# TL431_Fan_Control.net
KiCad netlist of a schematic drawn in EAGLE
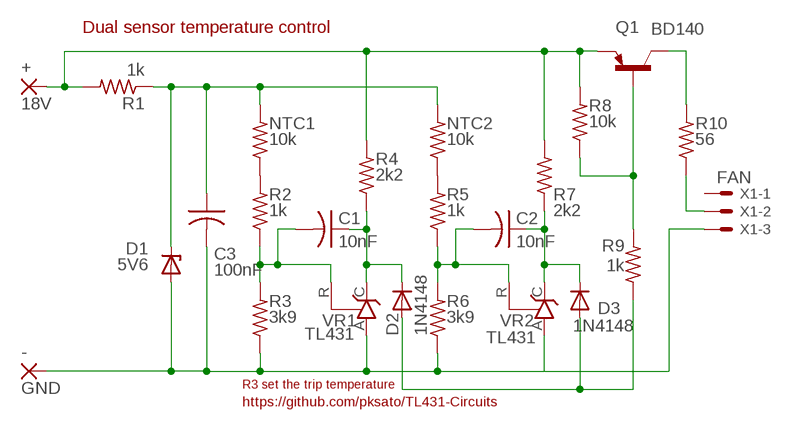
[diagram p0: schematic, sheet 1]

(export (version "E")
  (design (tool "Eeschema 10.0.6"))
  (components
    (comp (ref "+")
      (value "18V")
      (footprint "eagle-import:2,54_1,0")
      (libsource (lib "eagle-import") (part "WIREPAD2,54/1,0"))
    )
    (comp (ref "-")
      (value "GND")
      (footprint "eagle-import:2,54_1,0")
      (libsource (lib "eagle-import") (part "WIREPAD2,54/1,0"))
    )
    (comp (ref "C1")
      (value "10nF")
      (footprint "eagle-import:C050-024X044")
      (libsource (lib "eagle-import") (part "C-US050-024X044"))
    )
    (comp (ref "C2")
      (value "10nF")
      (footprint "eagle-import:C050-024X044")
      (libsource (lib "eagle-import") (part "C-US050-024X044"))
    )
    (comp (ref "C3")
      (value "100nF")
      (footprint "eagle-import:C050-024X044")
      (libsource (lib "eagle-import") (part "C-US050-024X044"))
    )
    (comp (ref "D1")
      (value "5V6")
      (footprint "eagle-import:ZDIO-7.5")
      (libsource (lib "eagle-import") (part "ZENER-DIODEZD-7.5"))
    )
    (comp (ref "D2")
      (value "1N4148")
      (footprint "eagle-import:D-5")
      (libsource (lib "eagle-import") (part "DIODE-D-5"))
    )
    (comp (ref "D3")
      (value "1N4148")
      (footprint "eagle-import:D-5")
      (libsource (lib "eagle-import") (part "DIODE-D-5"))
    )
    (comp (ref "NTC1")
      (value "10k")
      (footprint "eagle-import:0207_2V")
      (libsource (lib "eagle-import") (part "R-US_0207/2V"))
    )
    (comp (ref "NTC2")
      (value "10k")
      (footprint "eagle-import:0207_2V")
      (libsource (lib "eagle-import") (part "R-US_0207/2V"))
    )
    (comp (ref "Q1")
      (value "BD140")
      (footprint "eagle-import:TO126")
      (libsource (lib "eagle-import") (part "BD140"))
    )
    (comp (ref "R1")
      (value "1k")
      (footprint "eagle-import:0207_10")
      (libsource (lib "eagle-import") (part "R-US_0207/10"))
    )
    (comp (ref "R2")
      (value "1k")
      (footprint "eagle-import:0207_10")
      (libsource (lib "eagle-import") (part "R-US_0207/10"))
    )
    (comp (ref "R3")
      (value "3k9")
      (footprint "eagle-import:0207_10")
      (libsource (lib "eagle-import") (part "R-US_0207/10"))
    )
    (comp (ref "R4")
      (value "2k2")
      (footprint "eagle-import:0207_10")
      (libsource (lib "eagle-import") (part "R-US_0207/10"))
    )
    (comp (ref "R5")
      (value "1k")
      (footprint "eagle-import:0207_10")
      (libsource (lib "eagle-import") (part "R-US_0207/10"))
    )
    (comp (ref "R6")
      (value "3k9")
      (footprint "eagle-import:0207_10")
      (libsource (lib "eagle-import") (part "R-US_0207/10"))
    )
    (comp (ref "R7")
      (value "2k2")
      (footprint "eagle-import:0207_10")
      (libsource (lib "eagle-import") (part "R-US_0207/10"))
    )
    (comp (ref "R8")
      (value "10k")
      (footprint "eagle-import:0207_10")
      (libsource (lib "eagle-import") (part "R-US_0207/10"))
    )
    (comp (ref "R9")
      (value "1k")
      (footprint "eagle-import:0207_10")
      (libsource (lib "eagle-import") (part "R-US_0207/10"))
    )
    (comp (ref "R10")
      (value "56")
      (footprint "eagle-import:0617_22")
      (libsource (lib "eagle-import") (part "R-US_0617/22"))
    )
    (comp (ref "VR1")
      (value "TL431")
      (footprint "eagle-import:TO92-CLP")
      (libsource (lib "eagle-import") (part "TL431CLP"))
    )
    (comp (ref "VR2")
      (value "TL431")
      (footprint "eagle-import:TO92-CLP")
      (libsource (lib "eagle-import") (part "TL431CLP"))
    )
    (comp (ref "X1")
      (value "FAN")
      (footprint "eagle-import:22-23-2031")
      (fields (field (name "MF") "MOLEX") (field (name "MPN") "22-23-2031"))
      (libsource (lib "eagle-import") (part "22-23-2031"))
    )
  )
  (nets
    (net (code "1") (name "Net-(+-P)") (class "Default")
      (node (ref "+") (pin "1") (pinfunction "P_1") (pintype "passive"))
      (node (ref "Q1") (pin "1") (pinfunction "E_1") (pintype "passive"))
      (node (ref "R1") (pin "2") (pinfunction "2_2") (pintype "passive"))
      (node (ref "R4") (pin "2") (pinfunction "2_2") (pintype "passive"))
      (node (ref "R7") (pin "2") (pinfunction "2_2") (pintype "passive"))
      (node (ref "R8") (pin "2") (pinfunction "2_2") (pintype "passive"))
    )
    (net (code "2") (name "Net-(--P)") (class "Default")
      (node (ref "-") (pin "1") (pinfunction "P_1") (pintype "passive"))
      (node (ref "C3") (pin "2") (pinfunction "2_2") (pintype "passive"))
      (node (ref "D1") (pin "A") (pinfunction "A_A") (pintype "passive"))
      (node (ref "R3") (pin "1") (pinfunction "1_1") (pintype "passive"))
      (node (ref "R6") (pin "1") (pinfunction "1_1") (pintype "passive"))
      (node (ref "VR1") (pin "A") (pinfunction "A_A") (pintype "passive"))
      (node (ref "VR2") (pin "A") (pinfunction "A_A") (pintype "passive"))
      (node (ref "X1") (pin "3") (pinfunction "S_3") (pintype "passive"))
    )
    (net (code "3") (name "Net-(C1-Pad1)") (class "Default")
      (node (ref "C1") (pin "1") (pinfunction "1_1") (pintype "passive"))
      (node (ref "D2") (pin "C") (pinfunction "C_C") (pintype "passive"))
      (node (ref "R4") (pin "1") (pinfunction "1_1") (pintype "passive"))
      (node (ref "VR1") (pin "C") (pinfunction "C_C") (pintype "passive"))
    )
    (net (code "4") (name "Net-(C1-Pad2)") (class "Default")
      (node (ref "C1") (pin "2") (pinfunction "2_2") (pintype "passive"))
      (node (ref "R2") (pin "1") (pinfunction "1_1") (pintype "passive"))
      (node (ref "R3") (pin "2") (pinfunction "2_2") (pintype "passive"))
      (node (ref "VR1") (pin "R") (pinfunction "R_R") (pintype "passive"))
    )
    (net (code "5") (name "Net-(C2-Pad1)") (class "Default")
      (node (ref "C2") (pin "1") (pinfunction "1_1") (pintype "passive"))
      (node (ref "D3") (pin "C") (pinfunction "C_C") (pintype "passive"))
      (node (ref "R7") (pin "1") (pinfunction "1_1") (pintype "passive"))
      (node (ref "VR2") (pin "C") (pinfunction "C_C") (pintype "passive"))
    )
    (net (code "6") (name "Net-(C2-Pad2)") (class "Default")
      (node (ref "C2") (pin "2") (pinfunction "2_2") (pintype "passive"))
      (node (ref "R5") (pin "1") (pinfunction "1_1") (pintype "passive"))
      (node (ref "R6") (pin "2") (pinfunction "2_2") (pintype "passive"))
      (node (ref "VR2") (pin "R") (pinfunction "R_R") (pintype "passive"))
    )
    (net (code "7") (name "Net-(C3-Pad1)") (class "Default")
      (node (ref "C3") (pin "1") (pinfunction "1_1") (pintype "passive"))
      (node (ref "D1") (pin "C") (pinfunction "C_C") (pintype "passive"))
      (node (ref "NTC1") (pin "2") (pinfunction "2_2") (pintype "passive"))
      (node (ref "NTC2") (pin "2") (pinfunction "2_2") (pintype "passive"))
      (node (ref "R1") (pin "1") (pinfunction "1_1") (pintype "passive"))
    )
    (net (code "8") (name "Net-(D2-PadA)") (class "Default")
      (node (ref "D2") (pin "A") (pinfunction "A_A") (pintype "passive"))
      (node (ref "D3") (pin "A") (pinfunction "A_A") (pintype "passive"))
      (node (ref "R9") (pin "1") (pinfunction "1_1") (pintype "passive"))
    )
    (net (code "9") (name "Net-(NTC1-Pad1)") (class "Default")
      (node (ref "NTC1") (pin "1") (pinfunction "1_1") (pintype "passive"))
      (node (ref "R2") (pin "2") (pinfunction "2_2") (pintype "passive"))
    )
    (net (code "10") (name "Net-(NTC2-Pad1)") (class "Default")
      (node (ref "NTC2") (pin "1") (pinfunction "1_1") (pintype "passive"))
      (node (ref "R5") (pin "2") (pinfunction "2_2") (pintype "passive"))
    )
    (net (code "11") (name "Net-(Q1-B)") (class "Default")
      (node (ref "Q1") (pin "3") (pinfunction "B_3") (pintype "passive"))
      (node (ref "R8") (pin "1") (pinfunction "1_1") (pintype "passive"))
      (node (ref "R9") (pin "2") (pinfunction "2_2") (pintype "passive"))
    )
    (net (code "12") (name "Net-(Q1-C)") (class "Default")
      (node (ref "Q1") (pin "2") (pinfunction "C_2") (pintype "passive"))
      (node (ref "R10") (pin "2") (pinfunction "2_2") (pintype "passive"))
    )
    (net (code "13") (name "Net-(X1B-S)") (class "Default")
      (node (ref "R10") (pin "1") (pinfunction "1_1") (pintype "passive"))
      (node (ref "X1") (pin "2") (pinfunction "S_2") (pintype "passive"))
    )
    (net (code "14") (name "unconnected-(X1A-S-Pad1)") (class "Default")
      (node (ref "X1") (pin "1") (pinfunction "S_1") (pintype "passive"))
    )
  )
)
